# Baro.net
KiCad netlist of a schematic drawn in Altium Designer
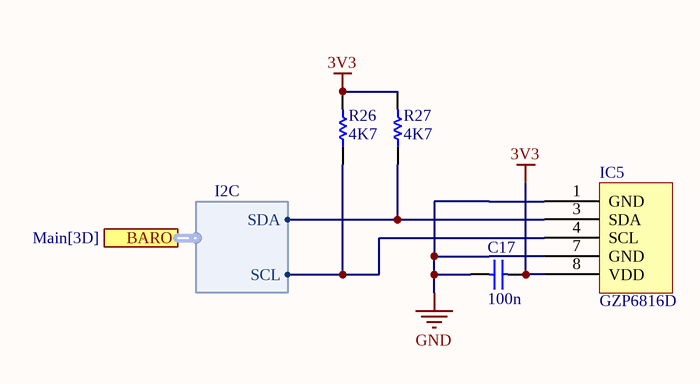
[diagram p0: Baro.SchDoc]

(export (version "E")
  (design (tool "Eeschema 10.0.6"))
  (components
    (comp (ref "C17")
      (value "100n")
      (footprint "CAPC0603(1608)55_N")
      (description "Keramikvielschichtkondensator, SMD, Baureihe MC, ± 20%")
      (fields (field (name "MANUFACTURER") "Multicomp"))
      (libsource (lib "Standardbauteile") (part "Cap 100n"))
    )
    (comp (ref "IC5")
      (value "GZP6816D")
      (footprint "GZP6816D")
      (libsource (lib "Custom Components") (part "GZP6816D"))
    )
    (comp (ref "R26")
      (value "4K7")
      (footprint "RESC0603(1608)_N")
      (description "Chipwiderstand, SMD, Baureihe MC, 5%")
      (fields (field (name "MANUFACTURER") "Multicomp"))
      (libsource (lib "Standardbauteile") (part "Res 4k7"))
    )
    (comp (ref "R27")
      (value "4K7")
      (footprint "RESC0603(1608)_N")
      (description "Chipwiderstand, SMD, Baureihe MC, 5%")
      (fields (field (name "MANUFACTURER") "Multicomp"))
      (libsource (lib "Standardbauteile") (part "Res 4k7"))
    )
  )
  (nets
    (net (code "3") (name "3V3") (class "Default")
      (node (ref "C17") (pin "1") (pinfunction "1_1") (pintype "passive"))
      (node (ref "IC5") (pin "8") (pinfunction "VDD_8") (pintype "passive"))
      (node (ref "R26") (pin "2") (pinfunction "2_2") (pintype "passive"))
      (node (ref "R27") (pin "2") (pinfunction "2_2") (pintype "passive"))
    )
    (net (code "4") (name "GND") (class "Default")
      (node (ref "C17") (pin "2") (pinfunction "2_2") (pintype "passive"))
      (node (ref "IC5") (pin "1") (pinfunction "GND_1") (pintype "passive"))
      (node (ref "IC5") (pin "7") (pinfunction "GND_7") (pintype "passive"))
    )
    (net (code "5") (name "Net-(IC5-SCL)") (class "Default")
      (node (ref "IC5") (pin "4") (pinfunction "SCL_4") (pintype "passive"))
      (node (ref "R26") (pin "1") (pinfunction "1_1") (pintype "passive"))
    )
    (net (code "6") (name "Net-(IC5-SDA)") (class "Default")
      (node (ref "IC5") (pin "3") (pinfunction "SDA_3") (pintype "passive"))
      (node (ref "R27") (pin "1") (pinfunction "1_1") (pintype "passive"))
    )
  )
)
